# projeto_teste.net
KiCad netlist of a schematic drawn in EAGLE
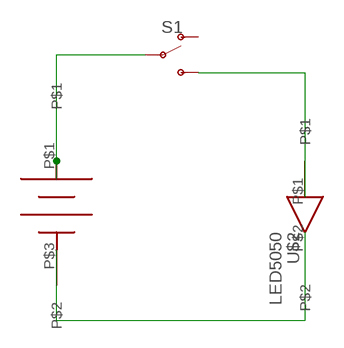
[diagram p0: schematic, sheet 1]

(export (version "E")
  (design (tool "Eeschema 10.0.6"))
  (components
    (comp (ref "S1")
      (value "SWITCH-SPDT-SMD-RIGHT-ANGLE")
      (footprint "eagle-import:SWITCH_SPST_SMD_A")
      (libsource (lib "eagle-import") (part "SWITCH-SPDT-SMD-RIGHT-ANGLE"))
    )
    (comp (ref "U$1")
      (value "CR2025")
      (footprint "eagle-import:CR2025")
      (libsource (lib "eagle-import") (part "CR2025"))
    )
    (comp (ref "U$2")
      (value "LED5050")
      (footprint "eagle-import:LED5050")
      (libsource (lib "eagle-import") (part "LED5050"))
    )
  )
  (nets
    (net (code "1") (name "Net-(S1-P)") (class "Default")
      (node (ref "S1") (pin "2") (pinfunction "P_2") (pintype "passive"))
      (node (ref "U$1") (pin "P$1") (pinfunction "P$1_P$1") (pintype "bidirectional"))
    )
    (net (code "2") (name "Net-(S1-S)") (class "Default")
      (node (ref "S1") (pin "3") (pinfunction "S_3") (pintype "passive"))
      (node (ref "U$2") (pin "P$1") (pinfunction "P$1_P$1") (pintype "bidirectional"))
    )
    (net (code "3") (name "Net-(U$1-P$2)") (class "Default")
      (node (ref "U$1") (pin "P$3") (pinfunction "P$2_P$3") (pintype "bidirectional"))
      (node (ref "U$2") (pin "P$2") (pinfunction "P$2_P$2") (pintype "bidirectional"))
    )
    (net (code "4") (name "unconnected-(S1-O-Pad1)") (class "Default")
      (node (ref "S1") (pin "1") (pinfunction "O_1") (pintype "passive"))
    )
  )
)
